# SilentStepStick-TMC5160_v13.net
KiCad netlist of a schematic drawn in EAGLE
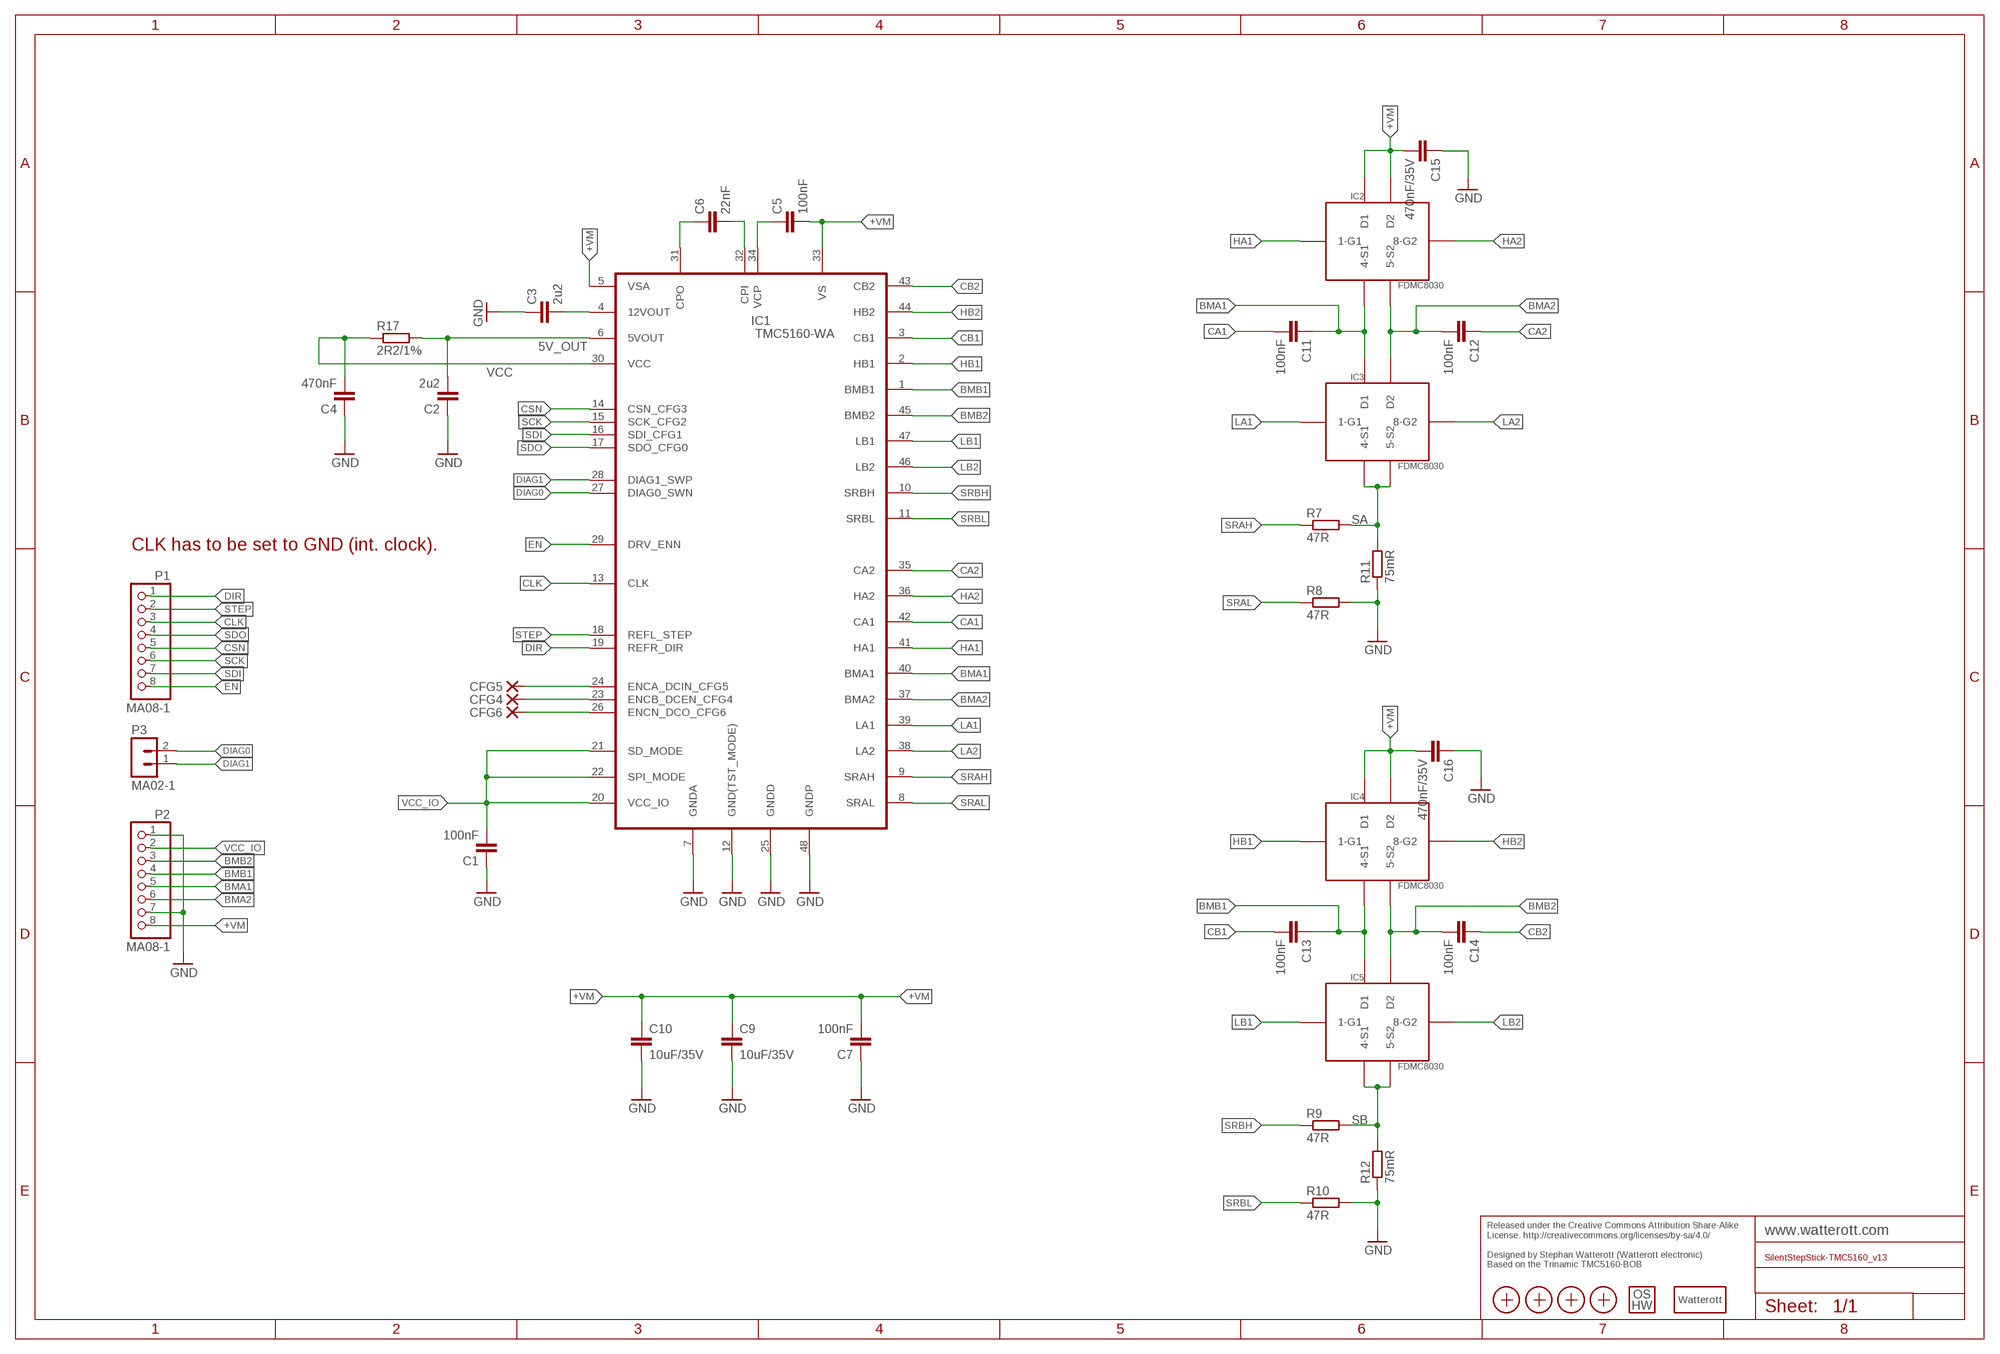
[diagram p0: schematic, sheet 1]

(export (version "E")
  (design (tool "Eeschema 10.0.6"))
  (components
    (comp (ref "C1")
      (value "100nF")
      (footprint "eagle-import:C0201")
      (libsource (lib "eagle-import") (part "C-EUC0201"))
    )
    (comp (ref "C2")
      (value "2u2")
      (footprint "eagle-import:C0402")
      (libsource (lib "eagle-import") (part "C-EUC0402"))
    )
    (comp (ref "C3")
      (value "2u2")
      (footprint "eagle-import:C0402")
      (libsource (lib "eagle-import") (part "C-EUC0402"))
    )
    (comp (ref "C4")
      (value "470nF")
      (footprint "eagle-import:C0402")
      (libsource (lib "eagle-import") (part "C-EUC0402"))
    )
    (comp (ref "C5")
      (value "100nF")
      (footprint "eagle-import:C0402")
      (libsource (lib "eagle-import") (part "C-EUC0402"))
    )
    (comp (ref "C6")
      (value "22nF")
      (footprint "eagle-import:C0402")
      (libsource (lib "eagle-import") (part "C-EUC0402"))
    )
    (comp (ref "C7")
      (value "100nF")
      (footprint "eagle-import:C0402")
      (libsource (lib "eagle-import") (part "C-EUC0402"))
    )
    (comp (ref "C9")
      (value "10uF/35V")
      (footprint "eagle-import:C0805")
      (libsource (lib "eagle-import") (part "C-EUC0805"))
    )
    (comp (ref "C10")
      (value "10uF/35V")
      (footprint "eagle-import:C0805")
      (libsource (lib "eagle-import") (part "C-EUC0805"))
    )
    (comp (ref "C11")
      (value "100nF")
      (footprint "eagle-import:C0402")
      (libsource (lib "eagle-import") (part "C-EUC0402"))
    )
    (comp (ref "C12")
      (value "100nF")
      (footprint "eagle-import:C0402")
      (libsource (lib "eagle-import") (part "C-EUC0402"))
    )
    (comp (ref "C13")
      (value "100nF")
      (footprint "eagle-import:C0402")
      (libsource (lib "eagle-import") (part "C-EUC0402"))
    )
    (comp (ref "C14")
      (value "100nF")
      (footprint "eagle-import:C0402")
      (libsource (lib "eagle-import") (part "C-EUC0402"))
    )
    (comp (ref "C15")
      (value "470nF/35V")
      (footprint "eagle-import:C0402")
      (libsource (lib "eagle-import") (part "C-EUC0402"))
    )
    (comp (ref "C16")
      (value "470nF/35V")
      (footprint "eagle-import:C0402")
      (libsource (lib "eagle-import") (part "C-EUC0402"))
    )
    (comp (ref "CFG4")
      (value "PAD-0.5_NC")
      (footprint "eagle-import:PAD-0.5_NC")
      (libsource (lib "eagle-import") (part "PAD-0.5_NC"))
    )
    (comp (ref "CFG5")
      (value "PAD-0.5_NC")
      (footprint "eagle-import:PAD-0.5_NC")
      (libsource (lib "eagle-import") (part "PAD-0.5_NC"))
    )
    (comp (ref "CFG6")
      (value "PAD-0.5_NC")
      (footprint "eagle-import:PAD-0.5_NC")
      (libsource (lib "eagle-import") (part "PAD-0.5_NC"))
    )
    (comp (ref "IC1")
      (value "TMC5160-WA")
      (footprint "eagle-import:VQFN56(47)_8.0X8.0X0.9MM_0.5P_EP")
      (libsource (lib "eagle-import") (part "TMC5160-WA"))
    )
    (comp (ref "IC2")
      (value "FDMC8030")
      (footprint "eagle-import:8-POWERWDFN")
      (libsource (lib "eagle-import") (part "FDMC8030"))
    )
    (comp (ref "IC3")
      (value "FDMC8030")
      (footprint "eagle-import:8-POWERWDFN")
      (libsource (lib "eagle-import") (part "FDMC8030"))
    )
    (comp (ref "IC4")
      (value "FDMC8030")
      (footprint "eagle-import:8-POWERWDFN")
      (libsource (lib "eagle-import") (part "FDMC8030"))
    )
    (comp (ref "IC5")
      (value "FDMC8030")
      (footprint "eagle-import:8-POWERWDFN")
      (libsource (lib "eagle-import") (part "FDMC8030"))
    )
    (comp (ref "LOGO1")
      (value "LOGO_SPARK-2")
      (footprint "eagle-import:SPARK_2MM")
      (libsource (lib "eagle-import") (part "LOGO_SPARK-2"))
    )
    (comp (ref "LOGO2")
      (value "LOGO_OSHW-2")
      (footprint "eagle-import:OSHW_2MM")
      (libsource (lib "eagle-import") (part "LOGO_OSHW-2"))
    )
    (comp (ref "P1")
      (value "MA08-1")
      (footprint "eagle-import:1X08-S")
      (libsource (lib "eagle-import") (part "PINHD-1X08_2.54-S"))
    )
    (comp (ref "P2")
      (value "MA08-1")
      (footprint "eagle-import:1X08-S")
      (libsource (lib "eagle-import") (part "PINHD-1X08_2.54-S"))
    )
    (comp (ref "P3")
      (value "MA02-1")
      (footprint "eagle-import:MA02-1")
      (libsource (lib "eagle-import") (part "MA02-1"))
    )
    (comp (ref "R7")
      (value "47R")
      (footprint "eagle-import:R0402")
      (libsource (lib "eagle-import") (part "R-EU_R0402"))
    )
    (comp (ref "R8")
      (value "47R")
      (footprint "eagle-import:R0402")
      (libsource (lib "eagle-import") (part "R-EU_R0402"))
    )
    (comp (ref "R9")
      (value "47R")
      (footprint "eagle-import:R0402")
      (libsource (lib "eagle-import") (part "R-EU_R0402"))
    )
    (comp (ref "R10")
      (value "47R")
      (footprint "eagle-import:R0402")
      (libsource (lib "eagle-import") (part "R-EU_R0402"))
    )
    (comp (ref "R11")
      (value "75mR")
      (footprint "eagle-import:R1206")
      (libsource (lib "eagle-import") (part "R-EU_R1206"))
    )
    (comp (ref "R12")
      (value "75mR")
      (footprint "eagle-import:R1206")
      (libsource (lib "eagle-import") (part "R-EU_R1206"))
    )
    (comp (ref "R17")
      (value "2R2/1%")
      (footprint "eagle-import:R0402")
      (libsource (lib "eagle-import") (part "R-EU_R0402"))
    )
    (comp (ref "X1")
      (value "PASSER-04")
      (footprint "eagle-import:PASSER_04MM")
      (libsource (lib "eagle-import") (part "PASSER-04"))
    )
    (comp (ref "X2")
      (value "PASSER-04")
      (footprint "eagle-import:PASSER_04MM")
      (libsource (lib "eagle-import") (part "PASSER-04"))
    )
    (comp (ref "X3")
      (value "PASSER-04")
      (footprint "eagle-import:PASSER_04MM")
      (libsource (lib "eagle-import") (part "PASSER-04"))
    )
    (comp (ref "X4")
      (value "PASSER-04")
      (footprint "eagle-import:PASSER_04MM")
      (libsource (lib "eagle-import") (part "PASSER-04"))
    )
  )
  (nets
    (net (code "1") (name "+VM") (class "Default")
      (node (ref "C10") (pin "1") (pinfunction "1_1") (pintype "passive"))
      (node (ref "C15") (pin "2") (pinfunction "2_2") (pintype "passive"))
      (node (ref "C16") (pin "2") (pinfunction "2_2") (pintype "passive"))
      (node (ref "C5") (pin "2") (pinfunction "2_2") (pintype "passive"))
      (node (ref "C7") (pin "2") (pinfunction "2_2") (pintype "passive"))
      (node (ref "C9") (pin "1") (pinfunction "1_1") (pintype "passive"))
      (node (ref "IC1") (pin "33") (pinfunction "VS_33") (pintype "power_in"))
      (node (ref "IC1") (pin "5") (pinfunction "VSA_5") (pintype "power_in"))
      (node (ref "IC2") (pin "P$D1") (pinfunction "D1_P$D1") (pintype "bidirectional"))
      (node (ref "IC2") (pin "P$D2") (pinfunction "D2_P$D2") (pintype "bidirectional"))
      (node (ref "IC4") (pin "P$D1") (pinfunction "D1_P$D1") (pintype "bidirectional"))
      (node (ref "IC4") (pin "P$D2") (pinfunction "D2_P$D2") (pintype "bidirectional"))
      (node (ref "P2") (pin "8") (pinfunction "8_8") (pintype "passive"))
    )
    (net (code "2") (name "/5V_OUT") (class "Default")
      (node (ref "C2") (pin "2") (pinfunction "2_2") (pintype "passive"))
      (node (ref "IC1") (pin "6") (pinfunction "5VOUT_6") (pintype "bidirectional"))
      (node (ref "R17") (pin "2") (pinfunction "2_2") (pintype "passive"))
    )
    (net (code "3") (name "/SA") (class "Default")
      (node (ref "IC3") (pin "P$4") (pinfunction "4-S1_P$4") (pintype "bidirectional"))
      (node (ref "IC3") (pin "P$5") (pinfunction "5-S2_P$5") (pintype "bidirectional"))
      (node (ref "R11") (pin "2") (pinfunction "2_2") (pintype "passive"))
      (node (ref "R7") (pin "2") (pinfunction "2_2") (pintype "passive"))
    )
    (net (code "4") (name "/SB") (class "Default")
      (node (ref "IC5") (pin "P$4") (pinfunction "4-S1_P$4") (pintype "bidirectional"))
      (node (ref "IC5") (pin "P$5") (pinfunction "5-S2_P$5") (pintype "bidirectional"))
      (node (ref "R12") (pin "2") (pinfunction "2_2") (pintype "passive"))
      (node (ref "R9") (pin "2") (pinfunction "2_2") (pintype "passive"))
    )
    (net (code "5") (name "/VCC") (class "Default")
      (node (ref "C4") (pin "2") (pinfunction "2_2") (pintype "passive"))
      (node (ref "IC1") (pin "30") (pinfunction "VCC_30") (pintype "power_in"))
      (node (ref "R17") (pin "1") (pinfunction "1_1") (pintype "passive"))
    )
    (net (code "6") (name "BMA1") (class "Default")
      (node (ref "C11") (pin "1") (pinfunction "1_1") (pintype "passive"))
      (node (ref "IC1") (pin "40") (pinfunction "BMA1_40") (pintype "input"))
      (node (ref "IC2") (pin "P$4") (pinfunction "4-S1_P$4") (pintype "bidirectional"))
      (node (ref "IC3") (pin "P$D1") (pinfunction "D1_P$D1") (pintype "bidirectional"))
      (node (ref "P2") (pin "5") (pinfunction "5_5") (pintype "passive"))
    )
    (net (code "7") (name "BMA2") (class "Default")
      (node (ref "C12") (pin "2") (pinfunction "2_2") (pintype "passive"))
      (node (ref "IC1") (pin "37") (pinfunction "BMA2_37") (pintype "input"))
      (node (ref "IC2") (pin "P$5") (pinfunction "5-S2_P$5") (pintype "bidirectional"))
      (node (ref "IC3") (pin "P$D2") (pinfunction "D2_P$D2") (pintype "bidirectional"))
      (node (ref "P2") (pin "6") (pinfunction "6_6") (pintype "passive"))
    )
    (net (code "8") (name "BMB1") (class "Default")
      (node (ref "C13") (pin "1") (pinfunction "1_1") (pintype "passive"))
      (node (ref "IC1") (pin "1") (pinfunction "BMB1_1") (pintype "input"))
      (node (ref "IC4") (pin "P$4") (pinfunction "4-S1_P$4") (pintype "bidirectional"))
      (node (ref "IC5") (pin "P$D1") (pinfunction "D1_P$D1") (pintype "bidirectional"))
      (node (ref "P2") (pin "4") (pinfunction "4_4") (pintype "passive"))
    )
    (net (code "9") (name "BMB2") (class "Default")
      (node (ref "C14") (pin "2") (pinfunction "2_2") (pintype "passive"))
      (node (ref "IC1") (pin "45") (pinfunction "BMB2_45") (pintype "input"))
      (node (ref "IC4") (pin "P$5") (pinfunction "5-S2_P$5") (pintype "bidirectional"))
      (node (ref "IC5") (pin "P$D2") (pinfunction "D2_P$D2") (pintype "bidirectional"))
      (node (ref "P2") (pin "3") (pinfunction "3_3") (pintype "passive"))
    )
    (net (code "10") (name "CA1") (class "Default")
      (node (ref "C11") (pin "2") (pinfunction "2_2") (pintype "passive"))
      (node (ref "IC1") (pin "42") (pinfunction "CA1_42") (pintype "input"))
    )
    (net (code "11") (name "CA2") (class "Default")
      (node (ref "C12") (pin "1") (pinfunction "1_1") (pintype "passive"))
      (node (ref "IC1") (pin "35") (pinfunction "CA2_35") (pintype "input"))
    )
    (net (code "12") (name "CB1") (class "Default")
      (node (ref "C13") (pin "2") (pinfunction "2_2") (pintype "passive"))
      (node (ref "IC1") (pin "3") (pinfunction "CB1_3") (pintype "input"))
    )
    (net (code "13") (name "CB2") (class "Default")
      (node (ref "C14") (pin "1") (pinfunction "1_1") (pintype "passive"))
      (node (ref "IC1") (pin "43") (pinfunction "CB2_43") (pintype "input"))
    )
    (net (code "14") (name "CLK") (class "Default")
      (node (ref "IC1") (pin "13") (pinfunction "CLK_13") (pintype "input"))
      (node (ref "P1") (pin "3") (pinfunction "3_3") (pintype "passive"))
    )
    (net (code "15") (name "CSN") (class "Default")
      (node (ref "IC1") (pin "14") (pinfunction "CSN_CFG3_14") (pintype "input"))
      (node (ref "P1") (pin "5") (pinfunction "5_5") (pintype "passive"))
    )
    (net (code "16") (name "DIAG0") (class "Default")
      (node (ref "IC1") (pin "27") (pinfunction "DIAG0_SWN_27") (pintype "bidirectional"))
      (node (ref "P3") (pin "2") (pinfunction "2_2") (pintype "passive"))
    )
    (net (code "17") (name "DIAG1") (class "Default")
      (node (ref "IC1") (pin "28") (pinfunction "DIAG1_SWP_28") (pintype "bidirectional"))
      (node (ref "P3") (pin "1") (pinfunction "1_1") (pintype "passive"))
    )
    (net (code "18") (name "DIR") (class "Default")
      (node (ref "IC1") (pin "19") (pinfunction "REFR_DIR_19") (pintype "input"))
      (node (ref "P1") (pin "1") (pinfunction "1_1") (pintype "passive"))
    )
    (net (code "19") (name "EN") (class "Default")
      (node (ref "IC1") (pin "29") (pinfunction "DRV_ENN_29") (pintype "input"))
      (node (ref "P1") (pin "8") (pinfunction "8_8") (pintype "passive"))
    )
    (net (code "20") (name "GND") (class "Default")
      (node (ref "C1") (pin "1") (pinfunction "1_1") (pintype "passive"))
      (node (ref "C10") (pin "2") (pinfunction "2_2") (pintype "passive"))
      (node (ref "C15") (pin "1") (pinfunction "1_1") (pintype "passive"))
      (node (ref "C16") (pin "1") (pinfunction "1_1") (pintype "passive"))
      (node (ref "C2") (pin "1") (pinfunction "1_1") (pintype "passive"))
      (node (ref "C3") (pin "1") (pinfunction "1_1") (pintype "passive"))
      (node (ref "C4") (pin "1") (pinfunction "1_1") (pintype "passive"))
      (node (ref "C7") (pin "1") (pinfunction "1_1") (pintype "passive"))
      (node (ref "C9") (pin "2") (pinfunction "2_2") (pintype "passive"))
      (node (ref "IC1") (pin "12") (pinfunction "GND(TST_MODE)_12") (pintype "input"))
      (node (ref "IC1") (pin "25") (pinfunction "GNDD_25") (pintype "power_in"))
      (node (ref "IC1") (pin "48") (pinfunction "GNDP_48") (pintype "power_in"))
      (node (ref "IC1") (pin "7") (pinfunction "GNDA_7") (pintype "power_in"))
      (node (ref "P2") (pin "1") (pinfunction "1_1") (pintype "passive"))
      (node (ref "P2") (pin "7") (pinfunction "7_7") (pintype "passive"))
      (node (ref "R10") (pin "2") (pinfunction "2_2") (pintype "passive"))
      (node (ref "R11") (pin "1") (pinfunction "1_1") (pintype "passive"))
      (node (ref "R12") (pin "1") (pinfunction "1_1") (pintype "passive"))
      (node (ref "R8") (pin "2") (pinfunction "2_2") (pintype "passive"))
    )
    (net (code "21") (name "HA1") (class "Default")
      (node (ref "IC1") (pin "41") (pinfunction "HA1_41") (pintype "output"))
      (node (ref "IC2") (pin "P$1") (pinfunction "1-G1_P$1") (pintype "bidirectional"))
    )
    (net (code "22") (name "HA2") (class "Default")
      (node (ref "IC1") (pin "36") (pinfunction "HA2_36") (pintype "output"))
      (node (ref "IC2") (pin "P$8") (pinfunction "8-G2_P$8") (pintype "bidirectional"))
    )
    (net (code "23") (name "HB1") (class "Default")
      (node (ref "IC1") (pin "2") (pinfunction "HB1_2") (pintype "output"))
      (node (ref "IC4") (pin "P$1") (pinfunction "1-G1_P$1") (pintype "bidirectional"))
    )
    (net (code "24") (name "HB2") (class "Default")
      (node (ref "IC1") (pin "44") (pinfunction "HB2_44") (pintype "output"))
      (node (ref "IC4") (pin "P$8") (pinfunction "8-G2_P$8") (pintype "bidirectional"))
    )
    (net (code "25") (name "LA1") (class "Default")
      (node (ref "IC1") (pin "39") (pinfunction "LA1_39") (pintype "output"))
      (node (ref "IC3") (pin "P$1") (pinfunction "1-G1_P$1") (pintype "bidirectional"))
    )
    (net (code "26") (name "LA2") (class "Default")
      (node (ref "IC1") (pin "38") (pinfunction "LA2_38") (pintype "output"))
      (node (ref "IC3") (pin "P$8") (pinfunction "8-G2_P$8") (pintype "bidirectional"))
    )
    (net (code "27") (name "LB1") (class "Default")
      (node (ref "IC1") (pin "47") (pinfunction "LB1_47") (pintype "output"))
      (node (ref "IC5") (pin "P$1") (pinfunction "1-G1_P$1") (pintype "bidirectional"))
    )
    (net (code "28") (name "LB2") (class "Default")
      (node (ref "IC1") (pin "46") (pinfunction "LB2_46") (pintype "output"))
      (node (ref "IC5") (pin "P$8") (pinfunction "8-G2_P$8") (pintype "bidirectional"))
    )
    (net (code "29") (name "Net-(CFG4-P)") (class "Default")
      (node (ref "CFG4") (pin "1") (pinfunction "P_1") (pintype "passive"))
      (node (ref "IC1") (pin "23") (pinfunction "ENCB_DCEN_CFG4_23") (pintype "input"))
    )
    (net (code "30") (name "Net-(CFG5-P)") (class "Default")
      (node (ref "CFG5") (pin "1") (pinfunction "P_1") (pintype "passive"))
      (node (ref "IC1") (pin "24") (pinfunction "ENCA_DCIN_CFG5_24") (pintype "input"))
    )
    (net (code "31") (name "Net-(CFG6-P)") (class "Default")
      (node (ref "CFG6") (pin "1") (pinfunction "P_1") (pintype "passive"))
      (node (ref "IC1") (pin "26") (pinfunction "ENCN_DCO_CFG6_26") (pintype "bidirectional"))
    )
    (net (code "32") (name "Net-(IC1-12VOUT)") (class "Default")
      (node (ref "C3") (pin "2") (pinfunction "2_2") (pintype "passive"))
      (node (ref "IC1") (pin "4") (pinfunction "12VOUT_4") (pintype "bidirectional"))
    )
    (net (code "33") (name "Net-(IC1-CPI)") (class "Default")
      (node (ref "C6") (pin "2") (pinfunction "2_2") (pintype "passive"))
      (node (ref "IC1") (pin "32") (pinfunction "CPI_32") (pintype "input"))
    )
    (net (code "34") (name "Net-(IC1-CPO)") (class "Default")
      (node (ref "C6") (pin "1") (pinfunction "1_1") (pintype "passive"))
      (node (ref "IC1") (pin "31") (pinfunction "CPO_31") (pintype "input"))
    )
    (net (code "35") (name "Net-(IC1-VCP)") (class "Default")
      (node (ref "C5") (pin "1") (pinfunction "1_1") (pintype "passive"))
      (node (ref "IC1") (pin "34") (pinfunction "VCP_34") (pintype "input"))
    )
    (net (code "36") (name "SCK") (class "Default")
      (node (ref "IC1") (pin "15") (pinfunction "SCK_CFG2_15") (pintype "input"))
      (node (ref "P1") (pin "6") (pinfunction "6_6") (pintype "passive"))
    )
    (net (code "37") (name "SDI") (class "Default")
      (node (ref "IC1") (pin "16") (pinfunction "SDI_CFG1_16") (pintype "input"))
      (node (ref "P1") (pin "7") (pinfunction "7_7") (pintype "passive"))
    )
    (net (code "38") (name "SDO") (class "Default")
      (node (ref "IC1") (pin "17") (pinfunction "SDO_CFG0_17") (pintype "bidirectional"))
      (node (ref "P1") (pin "4") (pinfunction "4_4") (pintype "passive"))
    )
    (net (code "39") (name "SRAH") (class "Default")
      (node (ref "IC1") (pin "9") (pinfunction "SRAH_9") (pintype "input"))
      (node (ref "R7") (pin "1") (pinfunction "1_1") (pintype "passive"))
    )
    (net (code "40") (name "SRAL") (class "Default")
      (node (ref "IC1") (pin "8") (pinfunction "SRAL_8") (pintype "input"))
      (node (ref "R8") (pin "1") (pinfunction "1_1") (pintype "passive"))
    )
    (net (code "41") (name "SRBH") (class "Default")
      (node (ref "IC1") (pin "10") (pinfunction "SRBH_10") (pintype "input"))
      (node (ref "R9") (pin "1") (pinfunction "1_1") (pintype "passive"))
    )
    (net (code "42") (name "SRBL") (class "Default")
      (node (ref "IC1") (pin "11") (pinfunction "SRBL_11") (pintype "input"))
      (node (ref "R10") (pin "1") (pinfunction "1_1") (pintype "passive"))
    )
    (net (code "43") (name "STEP") (class "Default")
      (node (ref "IC1") (pin "18") (pinfunction "REFL_STEP_18") (pintype "input"))
      (node (ref "P1") (pin "2") (pinfunction "2_2") (pintype "passive"))
    )
    (net (code "44") (name "VCC_IO") (class "Default")
      (node (ref "C1") (pin "2") (pinfunction "2_2") (pintype "passive"))
      (node (ref "IC1") (pin "20") (pinfunction "VCC_IO_20") (pintype "power_in"))
      (node (ref "IC1") (pin "21") (pinfunction "SD_MODE_21") (pintype "input"))
      (node (ref "IC1") (pin "22") (pinfunction "SPI_MODE_22") (pintype "input"))
      (node (ref "P2") (pin "2") (pinfunction "2_2") (pintype "passive"))
    )
  )
)
